# POWER_IN.net
KiCad netlist of a schematic drawn in Altium Designer
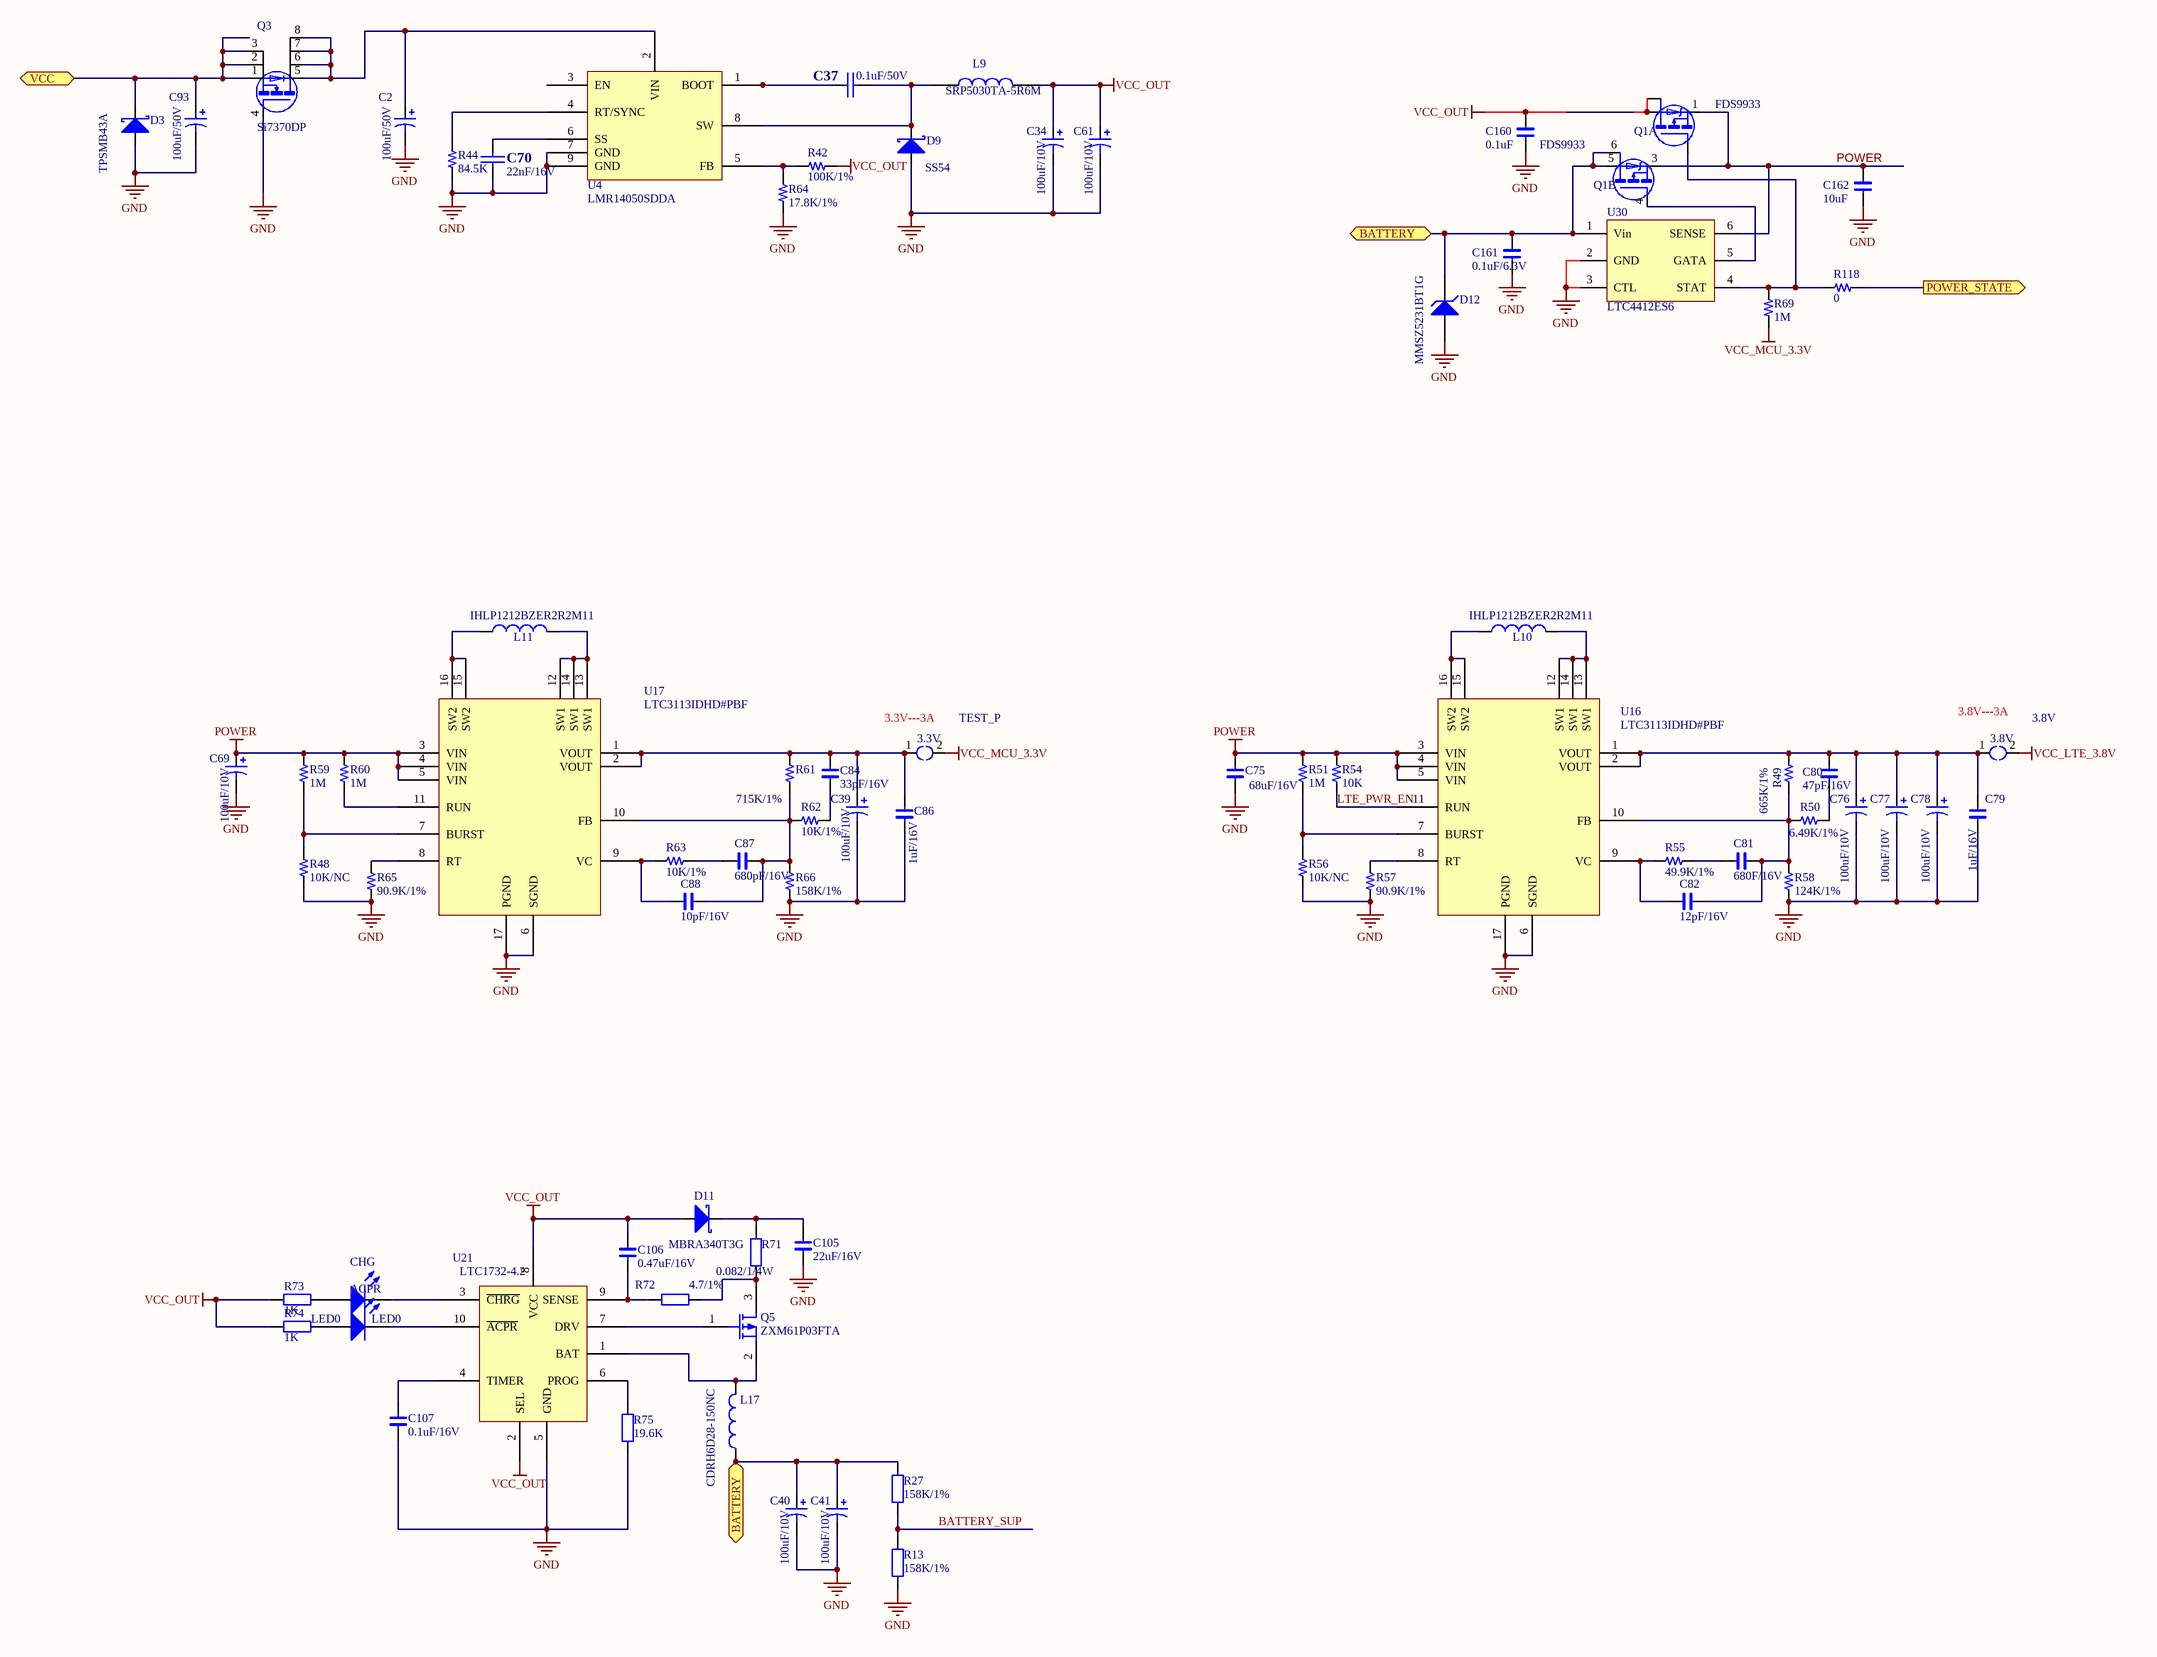
[diagram p0: POWER_IN.SchDoc]

(export (version "E")
  (design (tool "Eeschema 10.0.6"))
  (components
    (comp (ref "3.3V")
      (value "TEST_P")
      (footprint "Pcblib_20110825:TP_High PWR")
      (libsource (lib "Schlib_20110825") (part "TEST_P"))
    )
    (comp (ref "3.8V")
      (value "3.8V")
      (footprint "Pcblib_20110825:TP_High PWR")
      (description "TEST_P")
      (libsource (lib "Schlib_20110825") (part "TEST_P"))
    )
    (comp (ref "ACPR")
      (value "LED0")
      (footprint "0603LED")
      (description "Typical INFRARED GaAs LED")
      (fields (field (name "PUBLISHER") "Altium Limited"))
      (libsource (lib "Miscellaneous Devices") (part "LED0"))
    )
    (comp (ref "C2")
      (value "100uF/50V")
      (footprint "2220C")
      (description "Polarized Capacitor (Radial)")
      (fields (field (name "PUBLISHER") "Altium Limited"))
      (libsource (lib "Miscellaneous Devices") (part "Cap Pol1"))
    )
    (comp (ref "C34")
      (value "100uF/10V")
      (footprint "1210E")
      (description "Polarized Capacitor (Radial)")
      (fields (field (name "PUBLISHER") "Altium Limited"))
      (libsource (lib "Miscellaneous Devices") (part "Cap Pol1"))
    )
    (comp (ref "C37")
      (value "0.1uF/50V")
      (footprint "0603C")
      (description "Capacitor")
      (libsource (lib "*") (part "CAP"))
    )
    (comp (ref "C39")
      (value "100uF/10V")
      (footprint "1210E")
      (description "Polarized Capacitor (Radial)")
      (fields (field (name "PUBLISHER") "Altium Limited"))
      (libsource (lib "Miscellaneous Devices") (part "Cap Pol1"))
    )
    (comp (ref "C40")
      (value "100uF/10V")
      (footprint "1210E")
      (description "Polarized Capacitor (Radial)")
      (fields (field (name "PUBLISHER") "Altium Limited"))
      (libsource (lib "Miscellaneous Devices") (part "Cap Pol1"))
    )
    (comp (ref "C41")
      (value "100uF/10V")
      (footprint "1210E")
      (description "Polarized Capacitor (Radial)")
      (fields (field (name "PUBLISHER") "Altium Limited"))
      (libsource (lib "Miscellaneous Devices") (part "Cap Pol1"))
    )
    (comp (ref "C61")
      (value "100uF/10V")
      (footprint "1210E")
      (description "Polarized Capacitor (Radial)")
      (fields (field (name "PUBLISHER") "Altium Limited"))
      (libsource (lib "Miscellaneous Devices") (part "Cap Pol1"))
    )
    (comp (ref "C69")
      (value "100uF/10V")
      (footprint "1210E")
      (description "Polarized Capacitor (Radial)")
      (fields (field (name "PUBLISHER") "Altium Limited"))
      (libsource (lib "Miscellaneous Devices") (part "Cap Pol1"))
    )
    (comp (ref "C70")
      (value "22nF/16V")
      (footprint "0603C")
      (description "Capacitor")
      (libsource (lib "*") (part "CAP"))
    )
    (comp (ref "C75")
      (value "68uF/16V")
      (footprint "1206C")
      (description "C")
      (libsource (lib "Top") (part "C"))
    )
    (comp (ref "C76")
      (value "100uF/10V")
      (footprint "1210E")
      (description "Polarized Capacitor (Radial)")
      (fields (field (name "PUBLISHER") "Altium Limited"))
      (libsource (lib "Miscellaneous Devices") (part "Cap Pol1"))
    )
    (comp (ref "C77")
      (value "100uF/10V")
      (footprint "1210E")
      (description "Polarized Capacitor (Radial)")
      (fields (field (name "PUBLISHER") "Altium Limited"))
      (libsource (lib "Miscellaneous Devices") (part "Cap Pol1"))
    )
    (comp (ref "C78")
      (value "100uF/10V")
      (footprint "1210E")
      (description "Polarized Capacitor (Radial)")
      (fields (field (name "PUBLISHER") "Altium Limited"))
      (libsource (lib "Miscellaneous Devices") (part "Cap Pol1"))
    )
    (comp (ref "C79")
      (value "1uF/16V")
      (footprint "0603C")
      (description "C")
      (libsource (lib "Top") (part "C"))
    )
    (comp (ref "C80")
      (value "47pF/16V")
      (footprint "0603C")
      (description "C")
      (libsource (lib "Top") (part "C"))
    )
    (comp (ref "C81")
      (value "680F/16V")
      (footprint "0603C")
      (description "C")
      (libsource (lib "Top") (part "C"))
    )
    (comp (ref "C82")
      (value "12pF/16V")
      (footprint "0603C")
      (description "C")
      (libsource (lib "Top") (part "C"))
    )
    (comp (ref "C84")
      (value "33pF/16V")
      (footprint "0603C")
      (description "C")
      (libsource (lib "Top") (part "C"))
    )
    (comp (ref "C86")
      (value "1uF/16V")
      (footprint "0603C")
      (description "C")
      (libsource (lib "Top") (part "C"))
    )
    (comp (ref "C87")
      (value "680pF/16V")
      (footprint "0603C")
      (description "C")
      (libsource (lib "Top") (part "C"))
    )
    (comp (ref "C88")
      (value "10pF/16V")
      (footprint "0603C")
      (description "C")
      (libsource (lib "Top") (part "C"))
    )
    (comp (ref "C93")
      (value "100uF/50V")
      (footprint "2220C")
      (description "Polarized Capacitor (Radial)")
      (fields (field (name "PUBLISHER") "Altium Limited"))
      (libsource (lib "Miscellaneous Devices") (part "Cap Pol1"))
    )
    (comp (ref "C105")
      (value "22uF/16V")
      (footprint "0805C")
      (description "C")
      (libsource (lib "Top") (part "C"))
    )
    (comp (ref "C106")
      (value "0.47uF/16V")
      (footprint "0603C")
      (description "C")
      (libsource (lib "Top") (part "C"))
    )
    (comp (ref "C107")
      (value "0.1uF/16V")
      (footprint "0603C")
      (description "C")
      (libsource (lib "Top") (part "C"))
    )
    (comp (ref "C160") (value "0.1uF") (footprint "0603C") (description "C") (libsource (lib "*") (part "C")))
    (comp (ref "C161")
      (value "0.1uF/6.3V")
      (footprint "0603C")
      (description "C")
      (libsource (lib "*") (part "C"))
    )
    (comp (ref "C162") (value "10uF") (footprint "0603C") (description "C") (libsource (lib "*") (part "C")))
    (comp (ref "CHG")
      (value "LED0")
      (footprint "0603LED")
      (description "Typical INFRARED GaAs LED")
      (fields (field (name "PUBLISHER") "Altium Limited"))
      (libsource (lib "Miscellaneous Devices") (part "LED0"))
    )
    (comp (ref "D3")
      (value "TPSMB43A")
      (footprint "Pcblib_20110825:SMB")
      (description "Schottky Diode")
      (libsource (lib "*") (part "DIODE S"))
    )
    (comp (ref "D9")
      (value "SS54")
      (footprint "SMa")
      (description "Schottky Diode")
      (libsource (lib "*") (part "DIODE S"))
    )
    (comp (ref "D11")
      (value "MBRA340T3G")
      (footprint "SMA")
      (description "Schottky Diode")
      (libsource (lib "*") (part "DIODE S"))
    )
    (comp (ref "D12")
      (value "MMSZ5231BT1G")
      (footprint "Pcblib_20110825:SOD123")
      (description "Zener Diode")
      (fields (field (name "PUBLISHER") "Altium Limited"))
      (libsource (lib "Miscellaneous Devices") (part "D Zener"))
    )
    (comp (ref "L9") (value "SRP5030TA-5R6M") (footprint "SRP5030T") (libsource (lib "*") (part "INDUCTOR")))
    (comp (ref "L10")
      (value "IHLP1212BZER2R2M11")
      (footprint "Pcblib_20110825:IHLP-1212BZ")
      (description "Inductor")
      (fields (field (name "PUBLISHER") "Altium Limited"))
      (libsource (lib "Miscellaneous Devices") (part "Inductor"))
    )
    (comp (ref "L11")
      (value "IHLP1212BZER2R2M11")
      (footprint "Pcblib_20110825:IHLP-1212BZ")
      (description "Inductor")
      (fields (field (name "PUBLISHER") "Altium Limited"))
      (libsource (lib "Miscellaneous Devices") (part "Inductor"))
    )
    (comp (ref "L17")
      (value "CDRH6D28-150NC")
      (footprint "Pcblib_20110825:CDRH6D23")
      (description "Inductor")
      (fields (field (name "PUBLISHER") "Altium Limited"))
      (libsource (lib "Miscellaneous Devices") (part "Inductor"))
    )
    (comp (ref "Q1") (value "FDS9933") (footprint "FDS9933") (libsource (lib "*") (part "FDS4935")))
    (comp (ref "Q3")
      (value "Si7370DP")
      (footprint "PowerPAK SO-8")
      (libsource (lib "stm32") (part "BSC070N1ONS3"))
    )
    (comp (ref "Q5")
      (value "ZXM61P03FTA")
      (footprint "SOT23-3")
      (description "ZXM61P03F")
      (fields (field (name "PUBLISHER") "Altium Limited"))
      (libsource (lib "Miscellaneous Devices") (part "MOSFET-P"))
    )
    (comp (ref "R13")
      (value "158K/1%")
      (footprint "0603R")
      (description "Resistor")
      (fields (field (name "PUBLISHER") "Altium Limited"))
      (libsource (lib "") (part "Res2_1"))
    )
    (comp (ref "R27")
      (value "158K/1%")
      (footprint "0603R")
      (description "Resistor")
      (fields (field (name "PUBLISHER") "Altium Limited"))
      (libsource (lib "") (part "Res2_1"))
    )
    (comp (ref "R42")
      (value "100K/1%")
      (footprint "0603R")
      (description "R")
      (libsource (lib "JRJ_1") (part "R"))
    )
    (comp (ref "R44")
      (value "84.5K")
      (footprint "0603R")
      (description "R")
      (libsource (lib "JRJ_1") (part "R"))
    )
    (comp (ref "R48")
      (value "10K/NC")
      (footprint "0603R")
      (description "R")
      (libsource (lib "JRJ_1") (part "R"))
    )
    (comp (ref "R49")
      (value "665K/1%")
      (footprint "0603R")
      (description "R")
      (libsource (lib "JRJ_1") (part "R"))
    )
    (comp (ref "R50")
      (value "6.49K/1%")
      (footprint "0603R")
      (description "R")
      (libsource (lib "JRJ_1") (part "R"))
    )
    (comp (ref "R51") (value "1M") (footprint "0603R") (description "R") (libsource (lib "JRJ_1") (part "R")))
    (comp (ref "R54")
      (value "10K")
      (footprint "0603R")
      (description "R")
      (libsource (lib "JRJ_1") (part "R"))
    )
    (comp (ref "R55")
      (value "49.9K/1%")
      (footprint "0603R")
      (description "R")
      (libsource (lib "JRJ_1") (part "R"))
    )
    (comp (ref "R56")
      (value "10K/NC")
      (footprint "0603R")
      (description "R")
      (libsource (lib "JRJ_1") (part "R"))
    )
    (comp (ref "R57")
      (value "90.9K/1%")
      (footprint "0603R")
      (description "R")
      (libsource (lib "JRJ_1") (part "R"))
    )
    (comp (ref "R58")
      (value "124K/1%")
      (footprint "0603R")
      (description "R")
      (libsource (lib "JRJ_1") (part "R"))
    )
    (comp (ref "R59") (value "1M") (footprint "0603R") (description "R") (libsource (lib "JRJ_1") (part "R")))
    (comp (ref "R60") (value "1M") (footprint "0603R") (description "R") (libsource (lib "JRJ_1") (part "R")))
    (comp (ref "R61")
      (value "715K/1%")
      (footprint "0603R")
      (description "R")
      (libsource (lib "JRJ_1") (part "R"))
    )
    (comp (ref "R62")
      (value "10K/1%")
      (footprint "0603R")
      (description "R")
      (libsource (lib "JRJ_1") (part "R"))
    )
    (comp (ref "R63")
      (value "10K/1%")
      (footprint "0603R")
      (description "R")
      (libsource (lib "JRJ_1") (part "R"))
    )
    (comp (ref "R64")
      (value "17.8K/1%")
      (footprint "0603R")
      (description "R")
      (libsource (lib "JRJ_1") (part "R"))
    )
    (comp (ref "R65")
      (value "90.9K/1%")
      (footprint "0603R")
      (description "R")
      (libsource (lib "JRJ_1") (part "R"))
    )
    (comp (ref "R66")
      (value "158K/1%")
      (footprint "0603R")
      (description "R")
      (libsource (lib "JRJ_1") (part "R"))
    )
    (comp (ref "R69") (value "1M") (footprint "0603R") (description "R") (libsource (lib "") (part "R_1")))
    (comp (ref "R71")
      (value "0.082/1/4W")
      (footprint "2010R")
      (description "Resistor")
      (fields (field (name "PUBLISHER") "Altium Limited"))
      (libsource (lib "") (part "Res2_1"))
    )
    (comp (ref "R72")
      (value "4.7/1%")
      (footprint "0603R")
      (description "Resistor")
      (fields (field (name "PUBLISHER") "Altium Limited"))
      (libsource (lib "") (part "Res2_2"))
    )
    (comp (ref "R73")
      (value "1K")
      (footprint "0603R")
      (description "Resistor")
      (fields (field (name "PUBLISHER") "Altium Limited"))
      (libsource (lib "Miscellaneous Devices") (part "Res2"))
    )
    (comp (ref "R74")
      (value "1K")
      (footprint "0603R")
      (description "Resistor")
      (fields (field (name "PUBLISHER") "Altium Limited"))
      (libsource (lib "Miscellaneous Devices") (part "Res2"))
    )
    (comp (ref "R75")
      (value "19.6K")
      (footprint "0603R")
      (description "Resistor")
      (fields (field (name "PUBLISHER") "Altium Limited"))
      (libsource (lib "") (part "Res2_1"))
    )
    (comp (ref "R118") (value "0") (footprint "0603R") (description "R") (libsource (lib "*") (part "R")))
    (comp (ref "U4")
      (value "LMR14050SDDA")
      (footprint "SOP127P600X168_HS-8N")
      (libsource (lib "Schlib_20110825") (part "LMR14050SDDA"))
    )
    (comp (ref "U16")
      (value "LTC3113IDHD#PBF")
      (footprint "QFN50P400X500X80-16N")
      (libsource (lib "Schlib_20110825") (part "LTC3113IDHD#PBF"))
    )
    (comp (ref "U17")
      (value "LTC3113IDHD#PBF")
      (footprint "QFN50P400X500X80-16N")
      (libsource (lib "Schlib_20110825") (part "LTC3113IDHD#PBF"))
    )
    (comp (ref "U21")
      (value "LTC1732-4.2")
      (footprint "MSOP-10")
      (libsource (lib "Schlib_20110825") (part "LTC1732-4.2"))
    )
    (comp (ref "U30") (value "LTC4412ES6") (footprint "TSOT-23") (libsource (lib "*") (part "LTC4412")))
  )
  (nets
    (net (code "1") (name "/BATTERY") (class "Default")
      (node (ref "C161") (pin "2") (pintype "passive"))
      (node (ref "C40") (pin "1") (pinfunction "1_1") (pintype "passive"))
      (node (ref "C41") (pin "1") (pinfunction "1_1") (pintype "passive"))
      (node (ref "D12") (pin "K") (pinfunction "K_K") (pintype "passive"))
      (node (ref "L17") (pin "1") (pinfunction "1_1") (pintype "passive"))
      (node (ref "Q1") (pin "5") (pinfunction "D_5") (pintype "passive"))
      (node (ref "R27") (pin "2") (pinfunction "2_2") (pintype "passive"))
      (node (ref "U30") (pin "1") (pinfunction "Vin_1") (pintype "passive"))
    )
    (net (code "2") (name "/BATTERY_SUP") (class "Default")
      (node (ref "R13") (pin "2") (pinfunction "2_2") (pintype "passive"))
      (node (ref "R27") (pin "1") (pinfunction "1_1") (pintype "passive"))
    )
    (net (code "3") (name "/LTE_PWR_EN") (class "Default")
      (node (ref "R54") (pin "2") (pintype "passive"))
      (node (ref "U16") (pin "11") (pinfunction "RUN_11") (pintype "passive"))
    )
    (net (code "4") (name "/POWER_STATE") (class "Default") (node (ref "R118") (pin "2") (pintype "passive")))
    (net (code "5") (name "/VCC") (class "Default")
      (node (ref "C93") (pin "1") (pinfunction "1_1") (pintype "passive"))
      (node (ref "D3") (pin "2") (pinfunction "K_2") (pintype "passive"))
      (node (ref "Q3") (pin "1") (pinfunction "D_1") (pintype "passive"))
      (node (ref "Q3") (pin "2") (pinfunction "D_2") (pintype "passive"))
      (node (ref "Q3") (pin "3") (pinfunction "D_3") (pintype "passive"))
    )
    (net (code "6") (name "GND") (class "Default")
      (node (ref "C105") (pin "1") (pintype "passive"))
      (node (ref "C107") (pin "1") (pintype "passive"))
      (node (ref "C160") (pin "1") (pintype "passive"))
      (node (ref "C161") (pin "1") (pintype "passive"))
      (node (ref "C162") (pin "1") (pintype "passive"))
      (node (ref "C2") (pin "2") (pinfunction "2_2") (pintype "passive"))
      (node (ref "C34") (pin "2") (pinfunction "2_2") (pintype "passive"))
      (node (ref "C39") (pin "2") (pinfunction "2_2") (pintype "passive"))
      (node (ref "C40") (pin "2") (pinfunction "2_2") (pintype "passive"))
      (node (ref "C41") (pin "2") (pinfunction "2_2") (pintype "passive"))
      (node (ref "C61") (pin "2") (pinfunction "2_2") (pintype "passive"))
      (node (ref "C69") (pin "2") (pinfunction "2_2") (pintype "passive"))
      (node (ref "C70") (pin "2") (pinfunction "2_2") (pintype "passive"))
      (node (ref "C75") (pin "2") (pintype "passive"))
      (node (ref "C76") (pin "2") (pinfunction "2_2") (pintype "passive"))
      (node (ref "C77") (pin "2") (pinfunction "2_2") (pintype "passive"))
      (node (ref "C78") (pin "2") (pinfunction "2_2") (pintype "passive"))
      (node (ref "C79") (pin "2") (pintype "passive"))
      (node (ref "C86") (pin "2") (pintype "passive"))
      (node (ref "C93") (pin "2") (pinfunction "2_2") (pintype "passive"))
      (node (ref "D12") (pin "A") (pinfunction "A_A") (pintype "passive"))
      (node (ref "D3") (pin "1") (pinfunction "A_1") (pintype "passive"))
      (node (ref "D9") (pin "1") (pinfunction "A_1") (pintype "passive"))
      (node (ref "Q3") (pin "4") (pinfunction "G_4") (pintype "passive"))
      (node (ref "R13") (pin "1") (pinfunction "1_1") (pintype "passive"))
      (node (ref "R44") (pin "1") (pintype "passive"))
      (node (ref "R48") (pin "2") (pintype "passive"))
      (node (ref "R56") (pin "2") (pintype "passive"))
      (node (ref "R57") (pin "2") (pintype "passive"))
      (node (ref "R58") (pin "1") (pintype "passive"))
      (node (ref "R64") (pin "2") (pintype "passive"))
      (node (ref "R65") (pin "2") (pintype "passive"))
      (node (ref "R66") (pin "1") (pintype "passive"))
      (node (ref "R75") (pin "1") (pinfunction "1_1") (pintype "passive"))
      (node (ref "U16") (pin "17") (pinfunction "PGND_17") (pintype "passive"))
      (node (ref "U16") (pin "6") (pinfunction "SGND_6") (pintype "passive"))
      (node (ref "U17") (pin "17") (pinfunction "PGND_17") (pintype "passive"))
      (node (ref "U17") (pin "6") (pinfunction "SGND_6") (pintype "passive"))
      (node (ref "U21") (pin "5") (pinfunction "GND_5") (pintype "passive"))
      (node (ref "U30") (pin "2") (pinfunction "GND_2") (pintype "passive"))
      (node (ref "U30") (pin "3") (pinfunction "CTL_3") (pintype "passive"))
      (node (ref "U4") (pin "7") (pinfunction "GND_7") (pintype "passive"))
      (node (ref "U4") (pin "9") (pinfunction "GND_9") (pintype "passive"))
    )
    (net (code "7") (name "Net-(3.3V-Pad1)") (class "Default")
      (node (ref "3.3V") (pin "1") (pinfunction "1_1") (pintype "passive"))
      (node (ref "C39") (pin "1") (pinfunction "1_1") (pintype "passive"))
      (node (ref "C84") (pin "1") (pintype "passive"))
      (node (ref "C86") (pin "1") (pintype "passive"))
      (node (ref "R61") (pin "2") (pintype "passive"))
      (node (ref "U17") (pin "1") (pinfunction "VOUT_1") (pintype "passive"))
      (node (ref "U17") (pin "2") (pinfunction "VOUT_2") (pintype "passive"))
    )
    (net (code "8") (name "Net-(3.8V-Pad1)") (class "Default")
      (node (ref "3.8V") (pin "1") (pinfunction "1_1") (pintype "passive"))
      (node (ref "C76") (pin "1") (pinfunction "1_1") (pintype "passive"))
      (node (ref "C77") (pin "1") (pinfunction "1_1") (pintype "passive"))
      (node (ref "C78") (pin "1") (pinfunction "1_1") (pintype "passive"))
      (node (ref "C79") (pin "1") (pintype "passive"))
      (node (ref "C80") (pin "1") (pintype "passive"))
      (node (ref "R49") (pin "2") (pintype "passive"))
      (node (ref "U16") (pin "1") (pinfunction "VOUT_1") (pintype "passive"))
      (node (ref "U16") (pin "2") (pinfunction "VOUT_2") (pintype "passive"))
    )
    (net (code "9") (name "Net-(ACPR-A)") (class "Default")
      (node (ref "ACPR") (pin "1") (pinfunction "A_1") (pintype "passive"))
      (node (ref "R74") (pin "2") (pinfunction "2_2") (pintype "passive"))
    )
    (net (code "10") (name "Net-(ACPR-K)") (class "Default")
      (node (ref "ACPR") (pin "2") (pinfunction "K_2") (pintype "passive"))
      (node (ref "U21") (pin "10") (pinfunction "~{ACPR}_10") (pintype "passive"))
    )
    (net (code "11") (name "Net-(C80-Pad2)") (class "Default")
      (node (ref "C80") (pin "2") (pintype "passive"))
      (node (ref "R50") (pin "1") (pintype "passive"))
    )
    (net (code "12") (name "Net-(C81-Pad1)") (class "Default")
      (node (ref "C81") (pin "1") (pintype "passive"))
      (node (ref "R55") (pin "1") (pintype "passive"))
    )
    (net (code "13") (name "Net-(C84-Pad2)") (class "Default")
      (node (ref "C84") (pin "2") (pintype "passive"))
      (node (ref "R62") (pin "1") (pintype "passive"))
    )
    (net (code "14") (name "Net-(C87-Pad1)") (class "Default")
      (node (ref "C87") (pin "1") (pintype "passive"))
      (node (ref "R63") (pin "1") (pintype "passive"))
    )
    (net (code "15") (name "Net-(CHG-A)") (class "Default")
      (node (ref "CHG") (pin "1") (pinfunction "A_1") (pintype "passive"))
      (node (ref "R73") (pin "2") (pinfunction "2_2") (pintype "passive"))
    )
    (net (code "16") (name "Net-(CHG-K)") (class "Default")
      (node (ref "CHG") (pin "2") (pinfunction "K_2") (pintype "passive"))
      (node (ref "U21") (pin "3") (pinfunction "~{CHRG}_3") (pintype "passive"))
    )
    (net (code "17") (name "Net-(D9-K)") (class "Default")
      (node (ref "C37") (pin "1") (pinfunction "1_1") (pintype "passive"))
      (node (ref "D9") (pin "2") (pinfunction "K_2") (pintype "passive"))
      (node (ref "L9") (pin "1") (pinfunction "1_1") (pintype "passive"))
      (node (ref "U4") (pin "8") (pinfunction "SW_8") (pintype "passive"))
    )
    (net (code "18") (name "Net-(D11-K)") (class "Default")
      (node (ref "C105") (pin "2") (pintype "passive"))
      (node (ref "D11") (pin "2") (pinfunction "K_2") (pintype "passive"))
      (node (ref "R71") (pin "2") (pinfunction "2_2") (pintype "passive"))
    )
    (net (code "19") (name "Net-(L10-Pad1)") (class "Default")
      (node (ref "L10") (pin "1") (pinfunction "1_1") (pintype "passive"))
      (node (ref "U16") (pin "15") (pinfunction "SW2_15") (pintype "passive"))
      (node (ref "U16") (pin "16") (pinfunction "SW2_16") (pintype "passive"))
    )
    (net (code "20") (name "Net-(L10-Pad2)") (class "Default")
      (node (ref "L10") (pin "2") (pinfunction "2_2") (pintype "passive"))
      (node (ref "U16") (pin "12") (pinfunction "SW1_12") (pintype "passive"))
      (node (ref "U16") (pin "13") (pinfunction "SW1_13") (pintype "passive"))
      (node (ref "U16") (pin "14") (pinfunction "SW1_14") (pintype "passive"))
    )
    (net (code "21") (name "Net-(L11-Pad1)") (class "Default")
      (node (ref "L11") (pin "1") (pinfunction "1_1") (pintype "passive"))
      (node (ref "U17") (pin "15") (pinfunction "SW2_15") (pintype "passive"))
      (node (ref "U17") (pin "16") (pinfunction "SW2_16") (pintype "passive"))
    )
    (net (code "22") (name "Net-(L11-Pad2)") (class "Default")
      (node (ref "L11") (pin "2") (pinfunction "2_2") (pintype "passive"))
      (node (ref "U17") (pin "12") (pinfunction "SW1_12") (pintype "passive"))
      (node (ref "U17") (pin "13") (pinfunction "SW1_13") (pintype "passive"))
      (node (ref "U17") (pin "14") (pinfunction "SW1_14") (pintype "passive"))
    )
    (net (code "23") (name "Net-(Q1A-G)") (class "Default")
      (node (ref "Q1") (pin "2") (pinfunction "G_2") (pintype "passive"))
      (node (ref "R118") (pin "1") (pintype "passive"))
      (node (ref "R69") (pin "1") (pintype "passive"))
      (node (ref "U30") (pin "4") (pinfunction "STAT_4") (pintype "passive"))
    )
    (net (code "24") (name "Net-(Q1B-G)") (class "Default")
      (node (ref "Q1") (pin "4") (pinfunction "G_4") (pintype "passive"))
      (node (ref "U30") (pin "5") (pinfunction "GATA_5") (pintype "passive"))
    )
    (net (code "25") (name "Net-(Q3-S)") (class "Default")
      (node (ref "C2") (pin "1") (pinfunction "1_1") (pintype "passive"))
      (node (ref "Q3") (pin "5") (pinfunction "S_5") (pintype "passive"))
      (node (ref "Q3") (pin "6") (pinfunction "D_6") (pintype "passive"))
      (node (ref "Q3") (pin "7") (pinfunction "D1_7") (pintype "passive"))
      (node (ref "Q3") (pin "8") (pinfunction "D1_8") (pintype "passive"))
      (node (ref "U4") (pin "2") (pinfunction "VIN_2") (pintype "passive"))
    )
    (net (code "26") (name "Net-(Q5-D)") (class "Default")
      (node (ref "L17") (pin "2") (pinfunction "2_2") (pintype "passive"))
      (node (ref "Q5") (pin "2") (pinfunction "D_2") (pintype "passive"))
      (node (ref "U21") (pin "1") (pinfunction "BAT_1") (pintype "passive"))
    )
    (net (code "27") (name "Net-(Q5-G)") (class "Default")
      (node (ref "Q5") (pin "1") (pinfunction "G_1") (pintype "passive"))
      (node (ref "U21") (pin "7") (pinfunction "DRV_7") (pintype "passive"))
    )
    (net (code "28") (name "Net-(Q5-S)") (class "Default")
      (node (ref "Q5") (pin "3") (pinfunction "S_3") (pintype "passive"))
      (node (ref "R71") (pin "1") (pinfunction "1_1") (pintype "passive"))
      (node (ref "R72") (pin "1") (pinfunction "1_1") (pintype "passive"))
    )
    (net (code "29") (name "Net-(U4-BOOT)") (class "Default")
      (node (ref "C37") (pin "2") (pinfunction "2_2") (pintype "passive"))
      (node (ref "U4") (pin "1") (pinfunction "BOOT_1") (pintype "passive"))
    )
    (net (code "30") (name "Net-(U4-FB)") (class "Default")
      (node (ref "R42") (pin "1") (pintype "passive"))
      (node (ref "R64") (pin "1") (pintype "passive"))
      (node (ref "U4") (pin "5") (pinfunction "FB_5") (pintype "passive"))
    )
    (net (code "31") (name "Net-(U4-RT{slash}SYNC)") (class "Default")
      (node (ref "R44") (pin "2") (pintype "passive"))
      (node (ref "U4") (pin "4") (pinfunction "RT/SYNC_4") (pintype "passive"))
    )
    (net (code "32") (name "Net-(U4-SS)") (class "Default")
      (node (ref "C70") (pin "1") (pinfunction "1_1") (pintype "passive"))
      (node (ref "U4") (pin "6") (pinfunction "SS_6") (pintype "passive"))
    )
    (net (code "33") (name "Net-(U16-BURST)") (class "Default")
      (node (ref "R51") (pin "2") (pintype "passive"))
      (node (ref "R56") (pin "1") (pintype "passive"))
      (node (ref "U16") (pin "7") (pinfunction "BURST_7") (pintype "passive"))
    )
    (net (code "34") (name "Net-(U16-FB)") (class "Default")
      (node (ref "C81") (pin "2") (pintype "passive"))
      (node (ref "C82") (pin "2") (pintype "passive"))
      (node (ref "R49") (pin "1") (pintype "passive"))
      (node (ref "R50") (pin "2") (pintype "passive"))
      (node (ref "R58") (pin "2") (pintype "passive"))
      (node (ref "U16") (pin "10") (pinfunction "FB_10") (pintype "passive"))
    )
    (net (code "35") (name "Net-(U16-RT)") (class "Default")
      (node (ref "R57") (pin "1") (pintype "passive"))
      (node (ref "U16") (pin "8") (pinfunction "RT_8") (pintype "passive"))
    )
    (net (code "36") (name "Net-(U16-VC)") (class "Default")
      (node (ref "C82") (pin "1") (pintype "passive"))
      (node (ref "R55") (pin "2") (pintype "passive"))
      (node (ref "U16") (pin "9") (pinfunction "VC_9") (pintype "passive"))
    )
    (net (code "37") (name "Net-(U17-BURST)") (class "Default")
      (node (ref "R48") (pin "1") (pintype "passive"))
      (node (ref "R59") (pin "2") (pintype "passive"))
      (node (ref "U17") (pin "7") (pinfunction "BURST_7") (pintype "passive"))
    )
    (net (code "38") (name "Net-(U17-FB)") (class "Default")
      (node (ref "C87") (pin "2") (pintype "passive"))
      (node (ref "C88") (pin "2") (pintype "passive"))
      (node (ref "R61") (pin "1") (pintype "passive"))
      (node (ref "R62") (pin "2") (pintype "passive"))
      (node (ref "R66") (pin "2") (pintype "passive"))
      (node (ref "U17") (pin "10") (pinfunction "FB_10") (pintype "passive"))
    )
    (net (code "39") (name "Net-(U17-RT)") (class "Default")
      (node (ref "R65") (pin "1") (pintype "passive"))
      (node (ref "U17") (pin "8") (pinfunction "RT_8") (pintype "passive"))
    )
    (net (code "40") (name "Net-(U17-RUN)") (class "Default")
      (node (ref "R60") (pin "2") (pintype "passive"))
      (node (ref "U17") (pin "11") (pinfunction "RUN_11") (pintype "passive"))
    )
    (net (code "41") (name "Net-(U17-VC)") (class "Default")
      (node (ref "C88") (pin "1") (pintype "passive"))
      (node (ref "R63") (pin "2") (pintype "passive"))
      (node (ref "U17") (pin "9") (pinfunction "VC_9") (pintype "passive"))
    )
    (net (code "42") (name "Net-(U21-PROG)") (class "Default")
      (node (ref "R75") (pin "2") (pinfunction "2_2") (pintype "passive"))
      (node (ref "U21") (pin "6") (pinfunction "PROG_6") (pintype "passive"))
    )
    (net (code "43") (name "Net-(U21-SENSE)") (class "Default")
      (node (ref "C106") (pin "1") (pintype "passive"))
      (node (ref "R72") (pin "2") (pinfunction "2_2") (pintype "passive"))
      (node (ref "U21") (pin "9") (pinfunction "SENSE_9") (pintype "passive"))
    )
    (net (code "44") (name "Net-(U21-TIMER)") (class "Default")
      (node (ref "C107") (pin "2") (pintype "passive"))
      (node (ref "U21") (pin "4") (pinfunction "TIMER_4") (pintype "passive"))
    )
    (net (code "45") (name "POWER") (class "Default")
      (node (ref "C162") (pin "2") (pintype "passive"))
      (node (ref "C69") (pin "1") (pinfunction "1_1") (pintype "passive"))
      (node (ref "C75") (pin "1") (pintype "passive"))
      (node (ref "Q1") (pin "1") (pinfunction "S_1") (pintype "passive"))
      (node (ref "Q1") (pin "3") (pinfunction "S_3") (pintype "passive"))
      (node (ref "R51") (pin "1") (pintype "passive"))
      (node (ref "R54") (pin "1") (pintype "passive"))
      (node (ref "R59") (pin "1") (pintype "passive"))
      (node (ref "R60") (pin "1") (pintype "passive"))
      (node (ref "U16") (pin "3") (pinfunction "VIN_3") (pintype "passive"))
      (node (ref "U16") (pin "4") (pinfunction "VIN_4") (pintype "passive"))
      (node (ref "U16") (pin "5") (pinfunction "VIN_5") (pintype "passive"))
      (node (ref "U17") (pin "3") (pinfunction "VIN_3") (pintype "passive"))
      (node (ref "U17") (pin "4") (pinfunction "VIN_4") (pintype "passive"))
      (node (ref "U17") (pin "5") (pinfunction "VIN_5") (pintype "passive"))
      (node (ref "U30") (pin "6") (pinfunction "SENSE_6") (pintype "passive"))
    )
    (net (code "46") (name "VCC_LTE_3.8V") (class "Default")
      (node (ref "3.8V") (pin "2") (pinfunction "2_2") (pintype "passive"))
    )
    (net (code "47") (name "VCC_MCU_3.3V") (class "Default")
      (node (ref "3.3V") (pin "2") (pinfunction "2_2") (pintype "passive"))
      (node (ref "R69") (pin "2") (pintype "passive"))
    )
    (net (code "48") (name "VCC_OUT") (class "Default")
      (node (ref "C106") (pin "2") (pintype "passive"))
      (node (ref "C160") (pin "2") (pintype "passive"))
      (node (ref "C34") (pin "1") (pinfunction "1_1") (pintype "passive"))
      (node (ref "C61") (pin "1") (pinfunction "1_1") (pintype "passive"))
      (node (ref "D11") (pin "1") (pinfunction "A_1") (pintype "passive"))
      (node (ref "L9") (pin "2") (pinfunction "2_2") (pintype "passive"))
      (node (ref "Q1") (pin "7") (pinfunction "D_7") (pintype "passive"))
      (node (ref "Q1") (pin "8") (pinfunction "D_8") (pintype "passive"))
      (node (ref "R42") (pin "2") (pintype "passive"))
      (node (ref "R73") (pin "1") (pinfunction "1_1") (pintype "passive"))
      (node (ref "R74") (pin "1") (pinfunction "1_1") (pintype "passive"))
      (node (ref "U21") (pin "2") (pinfunction "SEL_2") (pintype "passive"))
      (node (ref "U21") (pin "8") (pinfunction "VCC_8") (pintype "passive"))
    )
    (net (code "49") (name "unconnected-(Q1B-D-Pad6)") (class "Default")
      (node (ref "Q1") (pin "6") (pinfunction "D_6") (pintype "passive"))
    )
    (net (code "50") (name "unconnected-(U4-EN-Pad3)") (class "Default")
      (node (ref "U4") (pin "3") (pinfunction "EN_3") (pintype "passive"))
    )
  )
)
